# QCopterFC_PWM_Sch.net
KiCad netlist of a schematic drawn in Altium Designer
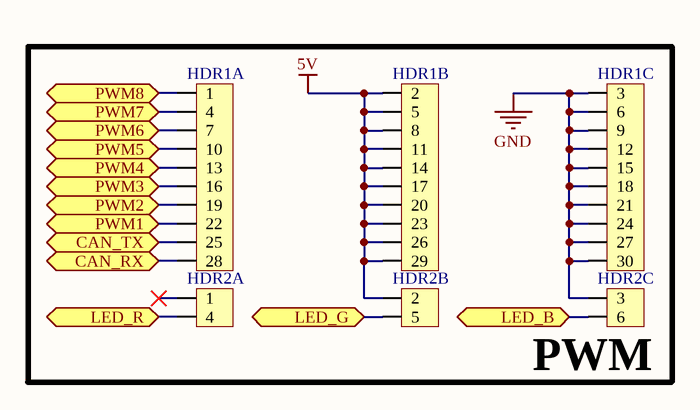
[diagram p0: QCopterFC_PWM_Sch.SchDoc]

(export (version "E")
  (design (tool "Eeschema 10.0.6"))
  (components
    (comp (ref "HDR1")
      (value "HDR3X10_90_2.54")
      (footprint "PCB_Connector:HDR3X10_90_2.54")
      (description "Header")
      (libsource (lib "SCH_Connector") (part "HDR3X10_90_2.54"))
    )
    (comp (ref "HDR2")
      (value "HDR3X2_90_2.54")
      (footprint "PCB_Connector:HDR3X2_90_2.54")
      (description "Header")
      (libsource (lib "SCH_Connector") (part "HDR3X2_90_2.54"))
    )
  )
  (nets
    (net (code "1") (name "/CAN_RX") (class "Default")
      (node (ref "HDR1") (pin "28") (pinfunction "28_28") (pintype "passive"))
    )
    (net (code "2") (name "/CAN_TX") (class "Default")
      (node (ref "HDR1") (pin "25") (pinfunction "25_25") (pintype "passive"))
    )
    (net (code "3") (name "/LED_B") (class "Default")
      (node (ref "HDR2") (pin "6") (pinfunction "6_6") (pintype "passive"))
    )
    (net (code "4") (name "/LED_G") (class "Default")
      (node (ref "HDR2") (pin "5") (pinfunction "5_5") (pintype "passive"))
    )
    (net (code "5") (name "/LED_R") (class "Default")
      (node (ref "HDR2") (pin "4") (pinfunction "4_4") (pintype "passive"))
    )
    (net (code "6") (name "/PWM1") (class "Default")
      (node (ref "HDR1") (pin "22") (pinfunction "22_22") (pintype "passive"))
    )
    (net (code "7") (name "/PWM2") (class "Default")
      (node (ref "HDR1") (pin "19") (pinfunction "19_19") (pintype "passive"))
    )
    (net (code "8") (name "/PWM3") (class "Default")
      (node (ref "HDR1") (pin "16") (pinfunction "16_16") (pintype "passive"))
    )
    (net (code "9") (name "/PWM4") (class "Default")
      (node (ref "HDR1") (pin "13") (pinfunction "13_13") (pintype "passive"))
    )
    (net (code "10") (name "/PWM5") (class "Default")
      (node (ref "HDR1") (pin "10") (pinfunction "10_10") (pintype "passive"))
    )
    (net (code "11") (name "/PWM6") (class "Default")
      (node (ref "HDR1") (pin "7") (pinfunction "7_7") (pintype "passive"))
    )
    (net (code "12") (name "/PWM7") (class "Default")
      (node (ref "HDR1") (pin "4") (pinfunction "4_4") (pintype "passive"))
    )
    (net (code "13") (name "/PWM8") (class "Default")
      (node (ref "HDR1") (pin "1") (pinfunction "1_1") (pintype "passive"))
    )
    (net (code "14") (name "5V") (class "Default")
      (node (ref "HDR1") (pin "11") (pinfunction "11_11") (pintype "passive"))
      (node (ref "HDR1") (pin "14") (pinfunction "14_14") (pintype "passive"))
      (node (ref "HDR1") (pin "17") (pinfunction "17_17") (pintype "passive"))
      (node (ref "HDR1") (pin "2") (pinfunction "2_2") (pintype "passive"))
      (node (ref "HDR1") (pin "20") (pinfunction "20_20") (pintype "passive"))
      (node (ref "HDR1") (pin "23") (pinfunction "23_23") (pintype "passive"))
      (node (ref "HDR1") (pin "26") (pinfunction "26_26") (pintype "passive"))
      (node (ref "HDR1") (pin "29") (pinfunction "29_29") (pintype "passive"))
      (node (ref "HDR1") (pin "5") (pinfunction "5_5") (pintype "passive"))
      (node (ref "HDR1") (pin "8") (pinfunction "8_8") (pintype "passive"))
      (node (ref "HDR2") (pin "2") (pinfunction "2_2") (pintype "passive"))
    )
    (net (code "15") (name "GND") (class "Default")
      (node (ref "HDR1") (pin "12") (pinfunction "12_12") (pintype "passive"))
      (node (ref "HDR1") (pin "15") (pinfunction "15_15") (pintype "passive"))
      (node (ref "HDR1") (pin "18") (pinfunction "18_18") (pintype "passive"))
      (node (ref "HDR1") (pin "21") (pinfunction "21_21") (pintype "passive"))
      (node (ref "HDR1") (pin "24") (pinfunction "24_24") (pintype "passive"))
      (node (ref "HDR1") (pin "27") (pinfunction "27_27") (pintype "passive"))
      (node (ref "HDR1") (pin "3") (pinfunction "3_3") (pintype "passive"))
      (node (ref "HDR1") (pin "30") (pinfunction "30_30") (pintype "passive"))
      (node (ref "HDR1") (pin "6") (pinfunction "6_6") (pintype "passive"))
      (node (ref "HDR1") (pin "9") (pinfunction "9_9") (pintype "passive"))
      (node (ref "HDR2") (pin "3") (pinfunction "3_3") (pintype "passive"))
    )
    (net (code "16") (name "unconnected-(HDR2-Pad1)") (class "Default")
      (node (ref "HDR2") (pin "1") (pinfunction "1_1") (pintype "passive+no_connect"))
    )
  )
)
